# H-BridgeAmpCore.net
KiCad netlist of a schematic drawn in EAGLE
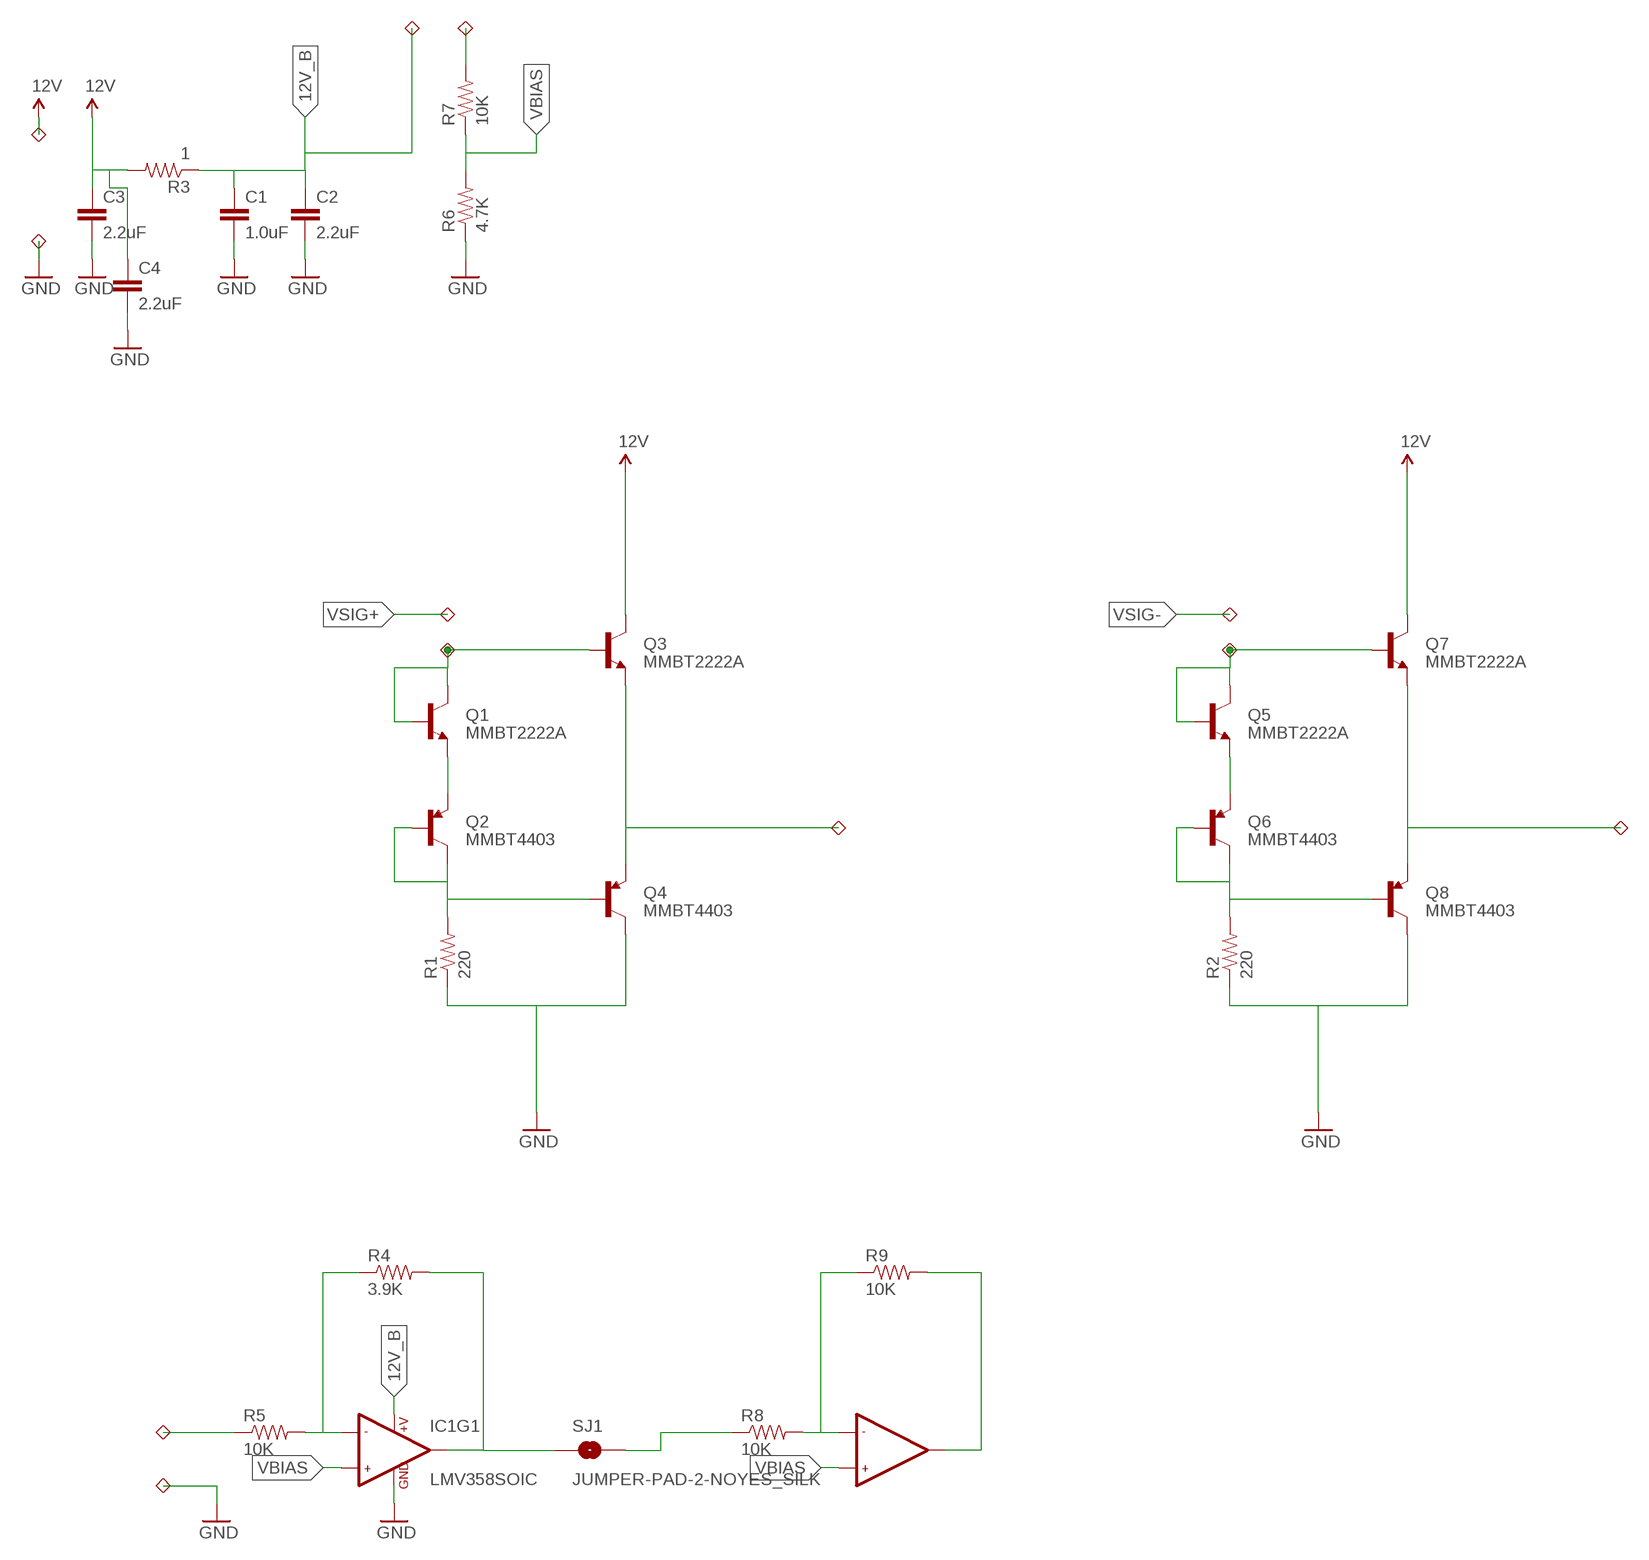
[diagram p0: schematic, sheet 1]

(export (version "E")
  (design (tool "Eeschema 10.0.6"))
  (components
    (comp (ref "C1")
      (value "1.0uF")
      (footprint "eagle-import:0603-CAP")
      (libsource (lib "eagle-import") (part "1.0UF-16V-10%(0603)"))
    )
    (comp (ref "C2")
      (value "2.2uF")
      (footprint "eagle-import:0805-CAP")
      (libsource (lib "eagle-import") (part "2.2UF-25V-+80/-20(0805)"))
    )
    (comp (ref "C3")
      (value "2.2uF")
      (footprint "eagle-import:0805-CAP")
      (libsource (lib "eagle-import") (part "2.2UF-25V-+80/-20(0805)"))
    )
    (comp (ref "C4")
      (value "2.2uF")
      (footprint "eagle-import:0805-CAP")
      (libsource (lib "eagle-import") (part "2.2UF-25V-+80/-20(0805)"))
    )
    (comp (ref "IC1")
      (value "LMV358SOIC")
      (footprint "eagle-import:SO08")
      (libsource (lib "eagle-import") (part "LMV358SOIC"))
    )
    (comp (ref "Q1")
      (value "MMBT2222A")
      (footprint "eagle-import:SOT23-3")
      (libsource (lib "eagle-import") (part "TRANSISTOR_NPNMMBT2222A"))
    )
    (comp (ref "Q2")
      (value "MMBT4403")
      (footprint "eagle-import:SOT23-3")
      (libsource (lib "eagle-import") (part "TRANSISTOR_PNPMMBT4403"))
    )
    (comp (ref "Q3")
      (value "MMBT2222A")
      (footprint "eagle-import:SOT23-3")
      (libsource (lib "eagle-import") (part "TRANSISTOR_NPNMMBT2222A"))
    )
    (comp (ref "Q4")
      (value "MMBT4403")
      (footprint "eagle-import:SOT23-3")
      (libsource (lib "eagle-import") (part "TRANSISTOR_PNPMMBT4403"))
    )
    (comp (ref "Q5")
      (value "MMBT2222A")
      (footprint "eagle-import:SOT23-3")
      (libsource (lib "eagle-import") (part "TRANSISTOR_NPNMMBT2222A"))
    )
    (comp (ref "Q6")
      (value "MMBT4403")
      (footprint "eagle-import:SOT23-3")
      (libsource (lib "eagle-import") (part "TRANSISTOR_PNPMMBT4403"))
    )
    (comp (ref "Q7")
      (value "MMBT2222A")
      (footprint "eagle-import:SOT23-3")
      (libsource (lib "eagle-import") (part "TRANSISTOR_NPNMMBT2222A"))
    )
    (comp (ref "Q8")
      (value "MMBT4403")
      (footprint "eagle-import:SOT23-3")
      (libsource (lib "eagle-import") (part "TRANSISTOR_PNPMMBT4403"))
    )
    (comp (ref "R1")
      (value "220")
      (footprint "eagle-import:0603-RES")
      (libsource (lib "eagle-import") (part "220OHM-1/10W-1%(0603)"))
    )
    (comp (ref "R2")
      (value "220")
      (footprint "eagle-import:0603-RES")
      (libsource (lib "eagle-import") (part "220OHM-1/10W-1%(0603)"))
    )
    (comp (ref "R3")
      (value "1")
      (footprint "eagle-import:0603-RES")
      (libsource (lib "eagle-import") (part "1OHM1/10W1%(0603)"))
    )
    (comp (ref "R4")
      (value "3.9K")
      (footprint "eagle-import:0603")
      (libsource (lib "eagle-import") (part "3.9KOHM1/10W1%(0603)"))
    )
    (comp (ref "R5")
      (value "10K")
      (footprint "eagle-import:0603-RES")
      (libsource (lib "eagle-import") (part "10KOHM-1/10W-1%(0603)0603"))
    )
    (comp (ref "R6")
      (value "4.7K")
      (footprint "eagle-import:0603-RES")
      (libsource (lib "eagle-import") (part "4.7KOHM-1/10W-1%(0603)"))
    )
    (comp (ref "R7")
      (value "10K")
      (footprint "eagle-import:0603-RES")
      (libsource (lib "eagle-import") (part "10KOHM-1/10W-1%(0603)0603"))
    )
    (comp (ref "R8")
      (value "10K")
      (footprint "eagle-import:0603-RES")
      (libsource (lib "eagle-import") (part "10KOHM-1/10W-1%(0603)0603"))
    )
    (comp (ref "R9")
      (value "10K")
      (footprint "eagle-import:0603-RES")
      (libsource (lib "eagle-import") (part "10KOHM-1/10W-1%(0603)0603"))
    )
    (comp (ref "SJ1")
      (value "JUMPER-PAD-2-NOYES_SILK")
      (footprint "eagle-import:PAD-JUMPER-2-NO_YES_SILK")
      (libsource (lib "eagle-import") (part "JUMPER-PAD-2-NOYES_SILK"))
    )
    (comp (ref "U$1")
      (value "1PIN")
      (footprint "eagle-import:THUMBNAIL")
      (libsource (lib "eagle-import") (part "1PIN"))
    )
    (comp (ref "U$2")
      (value "1PIN")
      (footprint "eagle-import:THUMBNAIL")
      (libsource (lib "eagle-import") (part "1PIN"))
    )
    (comp (ref "U$3")
      (value "1PIN")
      (footprint "eagle-import:THUMBNAIL")
      (libsource (lib "eagle-import") (part "1PIN"))
    )
    (comp (ref "U$4")
      (value "1PIN")
      (footprint "eagle-import:THUMBNAIL")
      (libsource (lib "eagle-import") (part "1PIN"))
    )
    (comp (ref "U$5")
      (value "1PIN")
      (footprint "eagle-import:THUMBNAIL")
      (libsource (lib "eagle-import") (part "1PIN"))
    )
    (comp (ref "U$6")
      (value "1PIN")
      (footprint "eagle-import:THUMBNAIL")
      (libsource (lib "eagle-import") (part "1PIN"))
    )
    (comp (ref "U$7")
      (value "1PINMINI")
      (footprint "eagle-import:THUMBNAILMINI")
      (libsource (lib "eagle-import") (part "1PINMINI"))
    )
    (comp (ref "U$8")
      (value "1PINMINI")
      (footprint "eagle-import:THUMBNAILMINI")
      (libsource (lib "eagle-import") (part "1PINMINI"))
    )
    (comp (ref "U$9")
      (value "1PINMINI")
      (footprint "eagle-import:THUMBNAILMINI")
      (libsource (lib "eagle-import") (part "1PINMINI"))
    )
    (comp (ref "U$10")
      (value "1PINMINI")
      (footprint "eagle-import:THUMBNAILMINI")
      (libsource (lib "eagle-import") (part "1PINMINI"))
    )
    (comp (ref "U$11")
      (value "1PINMINI")
      (footprint "eagle-import:THUMBNAILMINI")
      (libsource (lib "eagle-import") (part "1PINMINI"))
    )
    (comp (ref "U$12")
      (value "1PINMINI")
      (footprint "eagle-import:THUMBNAILMINI")
      (libsource (lib "eagle-import") (part "1PINMINI"))
    )
  )
  (nets
    (net (code "1") (name "12V") (class "Default")
      (node (ref "C3") (pin "1") (pinfunction "1_1") (pintype "passive"))
      (node (ref "C4") (pin "1") (pinfunction "1_1") (pintype "passive"))
      (node (ref "Q3") (pin "3") (pinfunction "C_3") (pintype "passive"))
      (node (ref "Q7") (pin "3") (pinfunction "C_3") (pintype "passive"))
      (node (ref "R3") (pin "2") (pinfunction "2_2") (pintype "passive"))
      (node (ref "U$5") (pin "P$1") (pinfunction "P$1_P$1") (pintype "bidirectional"))
    )
    (net (code "2") (name "12V_B") (class "Default")
      (node (ref "C1") (pin "1") (pinfunction "1_1") (pintype "passive"))
      (node (ref "C2") (pin "1") (pinfunction "1_1") (pintype "passive"))
      (node (ref "IC1") (pin "8") (pinfunction "+V_8") (pintype "power_in"))
      (node (ref "R3") (pin "1") (pinfunction "1_1") (pintype "passive"))
      (node (ref "U$11") (pin "P$1") (pinfunction "P$1_P$1") (pintype "bidirectional"))
    )
    (net (code "3") (name "GND") (class "Default")
      (node (ref "C1") (pin "2") (pinfunction "2_2") (pintype "passive"))
      (node (ref "C2") (pin "2") (pinfunction "2_2") (pintype "passive"))
      (node (ref "C3") (pin "2") (pinfunction "2_2") (pintype "passive"))
      (node (ref "C4") (pin "2") (pinfunction "2_2") (pintype "passive"))
      (node (ref "IC1") (pin "4") (pinfunction "GND_4") (pintype "power_in"))
      (node (ref "Q4") (pin "3") (pinfunction "C_3") (pintype "passive"))
      (node (ref "Q8") (pin "3") (pinfunction "C_3") (pintype "passive"))
      (node (ref "R1") (pin "1") (pinfunction "1_1") (pintype "passive"))
      (node (ref "R2") (pin "1") (pinfunction "1_1") (pintype "passive"))
      (node (ref "R6") (pin "1") (pinfunction "1_1") (pintype "passive"))
      (node (ref "U$4") (pin "P$1") (pinfunction "P$1_P$1") (pintype "bidirectional"))
      (node (ref "U$6") (pin "P$1") (pinfunction "P$1_P$1") (pintype "bidirectional"))
    )
    (net (code "4") (name "Net-(IC1A--IN1)") (class "Default")
      (node (ref "IC1") (pin "2") (pinfunction "-IN1_2") (pintype "input"))
      (node (ref "R4") (pin "1") (pinfunction "1_1") (pintype "passive"))
      (node (ref "R5") (pin "2") (pinfunction "2_2") (pintype "passive"))
    )
    (net (code "5") (name "Net-(IC1B--IN2)") (class "Default")
      (node (ref "IC1") (pin "6") (pinfunction "-IN2_6") (pintype "input"))
      (node (ref "R8") (pin "2") (pinfunction "2_2") (pintype "passive"))
      (node (ref "R9") (pin "1") (pinfunction "1_1") (pintype "passive"))
    )
    (net (code "6") (name "Net-(Q1-B)") (class "Default")
      (node (ref "Q1") (pin "1") (pinfunction "B_1") (pintype "passive"))
      (node (ref "Q1") (pin "3") (pinfunction "C_3") (pintype "passive"))
      (node (ref "Q3") (pin "1") (pinfunction "B_1") (pintype "passive"))
      (node (ref "U$9") (pin "P$1") (pinfunction "P$1_P$1") (pintype "bidirectional"))
    )
    (net (code "7") (name "Net-(Q1-E)") (class "Default")
      (node (ref "Q1") (pin "2") (pinfunction "E_2") (pintype "passive"))
      (node (ref "Q2") (pin "2") (pinfunction "E_2") (pintype "passive"))
    )
    (net (code "8") (name "Net-(Q2-B)") (class "Default")
      (node (ref "Q2") (pin "1") (pinfunction "B_1") (pintype "passive"))
      (node (ref "Q2") (pin "3") (pinfunction "C_3") (pintype "passive"))
      (node (ref "Q4") (pin "1") (pinfunction "B_1") (pintype "passive"))
      (node (ref "R1") (pin "2") (pinfunction "2_2") (pintype "passive"))
    )
    (net (code "9") (name "Net-(Q3-E)") (class "Default")
      (node (ref "Q3") (pin "2") (pinfunction "E_2") (pintype "passive"))
      (node (ref "Q4") (pin "2") (pinfunction "E_2") (pintype "passive"))
      (node (ref "U$2") (pin "P$1") (pinfunction "P$1_P$1") (pintype "bidirectional"))
    )
    (net (code "10") (name "Net-(Q5-B)") (class "Default")
      (node (ref "Q5") (pin "1") (pinfunction "B_1") (pintype "passive"))
      (node (ref "Q5") (pin "3") (pinfunction "C_3") (pintype "passive"))
      (node (ref "Q7") (pin "1") (pinfunction "B_1") (pintype "passive"))
      (node (ref "U$7") (pin "P$1") (pinfunction "P$1_P$1") (pintype "bidirectional"))
    )
    (net (code "11") (name "Net-(Q5-E)") (class "Default")
      (node (ref "Q5") (pin "2") (pinfunction "E_2") (pintype "passive"))
      (node (ref "Q6") (pin "2") (pinfunction "E_2") (pintype "passive"))
    )
    (net (code "12") (name "Net-(Q6-B)") (class "Default")
      (node (ref "Q6") (pin "1") (pinfunction "B_1") (pintype "passive"))
      (node (ref "Q6") (pin "3") (pinfunction "C_3") (pintype "passive"))
      (node (ref "Q8") (pin "1") (pinfunction "B_1") (pintype "passive"))
      (node (ref "R2") (pin "2") (pinfunction "2_2") (pintype "passive"))
    )
    (net (code "13") (name "Net-(Q7-E)") (class "Default")
      (node (ref "Q7") (pin "2") (pinfunction "E_2") (pintype "passive"))
      (node (ref "Q8") (pin "2") (pinfunction "E_2") (pintype "passive"))
      (node (ref "U$1") (pin "P$1") (pinfunction "P$1_P$1") (pintype "bidirectional"))
    )
    (net (code "14") (name "Net-(R5-Pad1)") (class "Default")
      (node (ref "R5") (pin "1") (pinfunction "1_1") (pintype "passive"))
      (node (ref "U$3") (pin "P$1") (pinfunction "P$1_P$1") (pintype "bidirectional"))
    )
    (net (code "15") (name "Net-(R7-Pad2)") (class "Default")
      (node (ref "R7") (pin "2") (pinfunction "2_2") (pintype "passive"))
      (node (ref "U$12") (pin "P$1") (pinfunction "P$1_P$1") (pintype "bidirectional"))
    )
    (net (code "16") (name "Net-(R8-Pad1)") (class "Default")
      (node (ref "R8") (pin "1") (pinfunction "1_1") (pintype "passive"))
      (node (ref "SJ1") (pin "2") (pinfunction "2_2") (pintype "passive"))
    )
    (net (code "17") (name "VBIAS") (class "Default")
      (node (ref "IC1") (pin "3") (pinfunction "+IN1_3") (pintype "input"))
      (node (ref "IC1") (pin "5") (pinfunction "+IN2_5") (pintype "input"))
      (node (ref "R6") (pin "2") (pinfunction "2_2") (pintype "passive"))
      (node (ref "R7") (pin "1") (pinfunction "1_1") (pintype "passive"))
    )
    (net (code "18") (name "VSIG+") (class "Default")
      (node (ref "IC1") (pin "1") (pinfunction "OUT1_1") (pintype "output"))
      (node (ref "R4") (pin "2") (pinfunction "2_2") (pintype "passive"))
      (node (ref "SJ1") (pin "1") (pinfunction "1_1") (pintype "passive"))
      (node (ref "U$10") (pin "P$1") (pinfunction "P$1_P$1") (pintype "bidirectional"))
    )
    (net (code "19") (name "VSIG-") (class "Default")
      (node (ref "IC1") (pin "7") (pinfunction "OUT2_7") (pintype "output"))
      (node (ref "R9") (pin "2") (pinfunction "2_2") (pintype "passive"))
      (node (ref "U$8") (pin "P$1") (pinfunction "P$1_P$1") (pintype "bidirectional"))
    )
  )
)
